# CANMosfetExtension.net
KiCad netlist of a schematic drawn in EAGLE
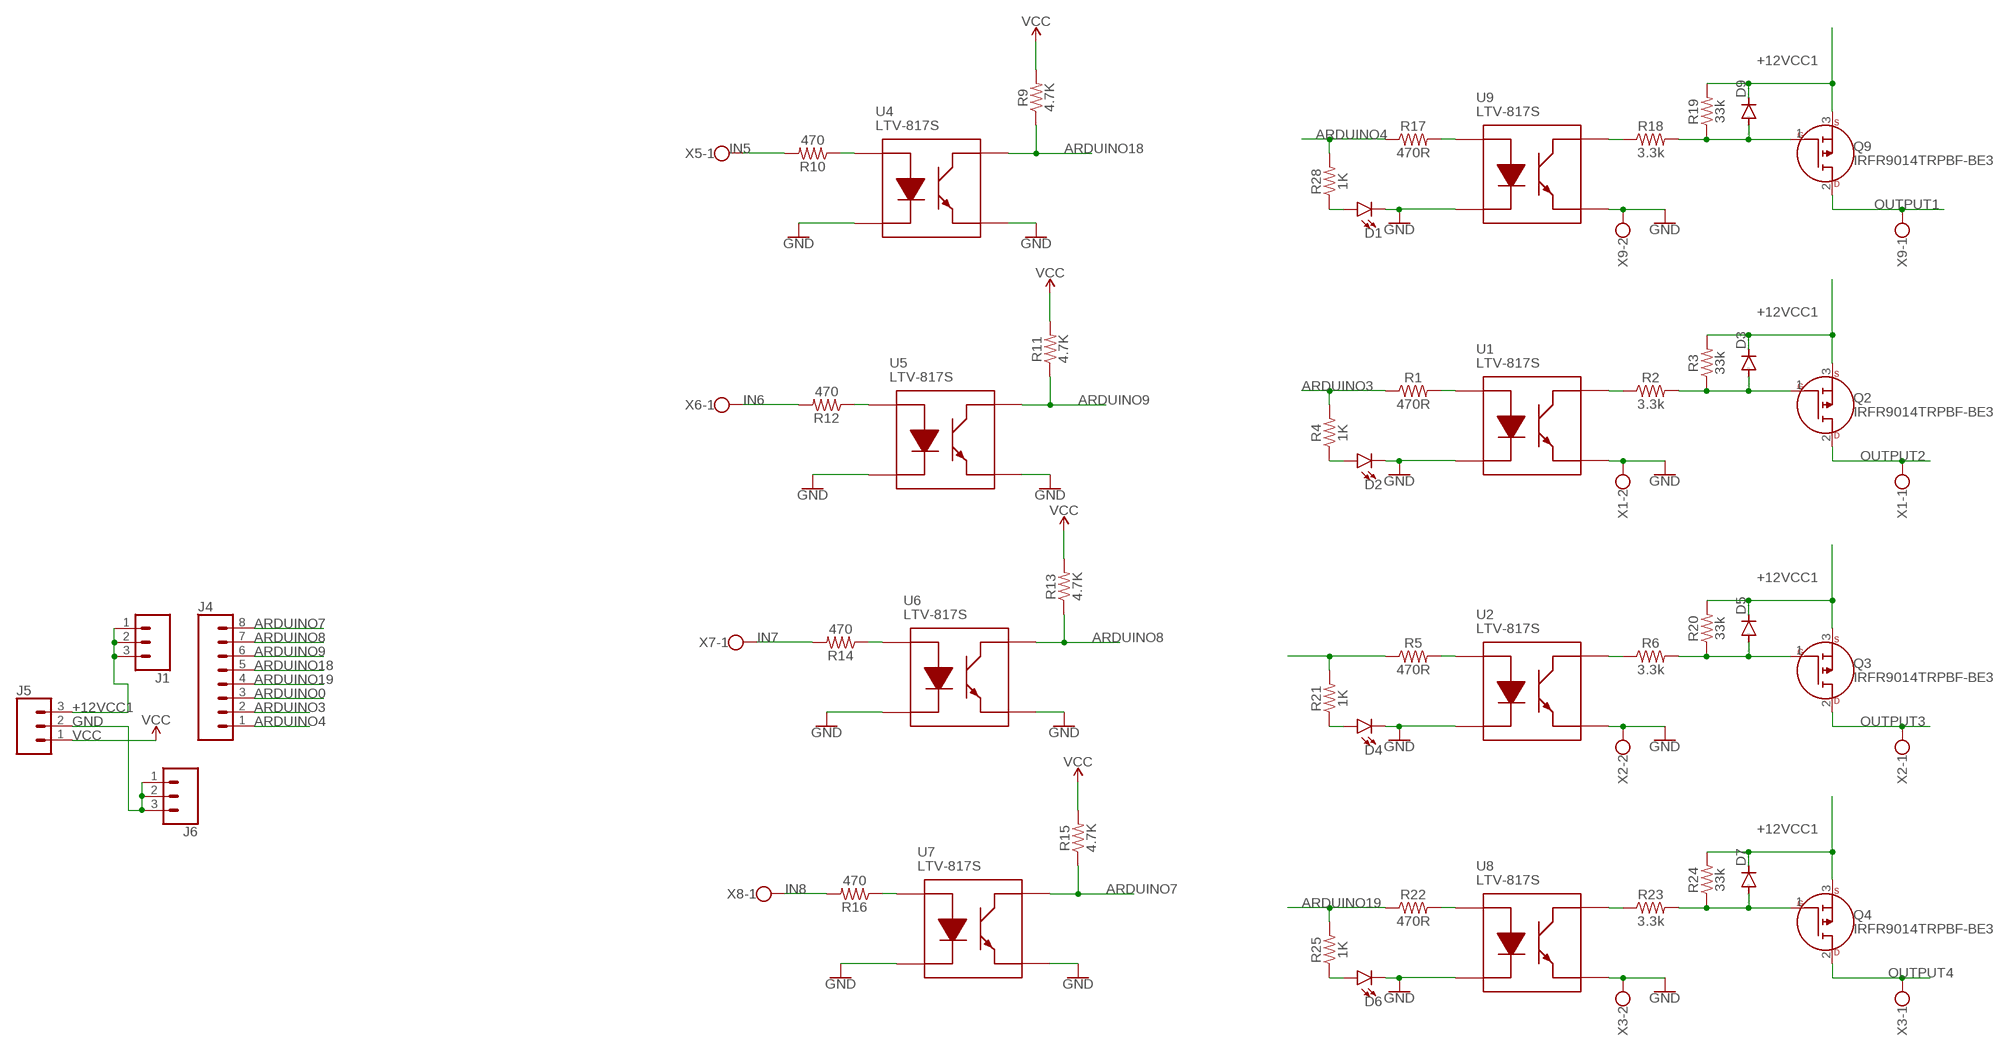
[diagram p0: schematic, sheet 1]

(export (version "E")
  (design (tool "Eeschema 10.0.6"))
  (components
    (comp (ref "D1")
      (value "LED0603")
      (footprint "eagle-import:LED-0603")
      (libsource (lib "eagle-import") (part "LED0603"))
    )
    (comp (ref "D2")
      (value "LED0603")
      (footprint "eagle-import:LED-0603")
      (libsource (lib "eagle-import") (part "LED0603"))
    )
    (comp (ref "D3")
      (value "DIODE-SOD123")
      (footprint "eagle-import:SOD123")
      (libsource (lib "eagle-import") (part "DIODE-SOD123"))
    )
    (comp (ref "D4")
      (value "LED0603")
      (footprint "eagle-import:LED-0603")
      (libsource (lib "eagle-import") (part "LED0603"))
    )
    (comp (ref "D5")
      (value "DIODE-SOD123")
      (footprint "eagle-import:SOD123")
      (libsource (lib "eagle-import") (part "DIODE-SOD123"))
    )
    (comp (ref "D6")
      (value "LED0603")
      (footprint "eagle-import:LED-0603")
      (libsource (lib "eagle-import") (part "LED0603"))
    )
    (comp (ref "D7")
      (value "DIODE-SOD123")
      (footprint "eagle-import:SOD123")
      (libsource (lib "eagle-import") (part "DIODE-SOD123"))
    )
    (comp (ref "D9")
      (value "DIODE-SOD123")
      (footprint "eagle-import:SOD123")
      (libsource (lib "eagle-import") (part "DIODE-SOD123"))
    )
    (comp (ref "J1")
      (value "CONN_03LOCK")
      (footprint "eagle-import:1X03_LOCK")
      (libsource (lib "eagle-import") (part "CONN_03LOCK"))
    )
    (comp (ref "J4")
      (value "CONN_08LOCK")
      (footprint "eagle-import:1X08_LOCK")
      (libsource (lib "eagle-import") (part "CONN_08LOCK"))
    )
    (comp (ref "J5")
      (value "CONN_03LOCK")
      (footprint "eagle-import:1X03_LOCK")
      (libsource (lib "eagle-import") (part "CONN_03LOCK"))
    )
    (comp (ref "J6")
      (value "CONN_03LOCK")
      (footprint "eagle-import:1X03_LOCK")
      (libsource (lib "eagle-import") (part "CONN_03LOCK"))
    )
    (comp (ref "Q2")
      (value "IRFR9014TRPBF-BE3")
      (footprint "eagle-import:IRFR9014TRPBFBE3")
      (fields (field (name "MOUSER_PART_NUMBER") "78-IRFR9014TRPBF-BE3"))
      (libsource (lib "eagle-import") (part "IRFR9014TRPBF-BE3"))
    )
    (comp (ref "Q3")
      (value "IRFR9014TRPBF-BE3")
      (footprint "eagle-import:IRFR9014TRPBFBE3")
      (fields (field (name "MOUSER_PART_NUMBER") "78-IRFR9014TRPBF-BE3"))
      (libsource (lib "eagle-import") (part "IRFR9014TRPBF-BE3"))
    )
    (comp (ref "Q4")
      (value "IRFR9014TRPBF-BE3")
      (footprint "eagle-import:IRFR9014TRPBFBE3")
      (fields (field (name "MOUSER_PART_NUMBER") "78-IRFR9014TRPBF-BE3"))
      (libsource (lib "eagle-import") (part "IRFR9014TRPBF-BE3"))
    )
    (comp (ref "Q9")
      (value "IRFR9014TRPBF-BE3")
      (footprint "eagle-import:IRFR9014TRPBFBE3")
      (fields (field (name "MOUSER_PART_NUMBER") "78-IRFR9014TRPBF-BE3"))
      (libsource (lib "eagle-import") (part "IRFR9014TRPBF-BE3"))
    )
    (comp (ref "R1")
      (value "470R")
      (footprint "eagle-import:0603")
      (libsource (lib "eagle-import") (part "1KOHM-0603-1/10W-1%"))
    )
    (comp (ref "R2")
      (value "3.3k")
      (footprint "eagle-import:0603")
      (libsource (lib "eagle-import") (part "1KOHM-0603-1/10W-1%"))
    )
    (comp (ref "R3")
      (value "33k")
      (footprint "eagle-import:0603")
      (libsource (lib "eagle-import") (part "1KOHM-0603-1/10W-1%"))
    )
    (comp (ref "R4")
      (value "1K")
      (footprint "eagle-import:0603")
      (libsource (lib "eagle-import") (part "1KOHM-0603-1/10W-1%"))
    )
    (comp (ref "R5")
      (value "470R")
      (footprint "eagle-import:0603")
      (libsource (lib "eagle-import") (part "1KOHM-0603-1/10W-1%"))
    )
    (comp (ref "R6")
      (value "3.3k")
      (footprint "eagle-import:0603")
      (libsource (lib "eagle-import") (part "1KOHM-0603-1/10W-1%"))
    )
    (comp (ref "R9")
      (value "4.7K")
      (footprint "eagle-import:0603")
      (libsource (lib "eagle-import") (part "1KOHM-0603-1/10W-1%"))
    )
    (comp (ref "R10")
      (value "470")
      (footprint "eagle-import:0603")
      (libsource (lib "eagle-import") (part "1KOHM-0603-1/10W-1%"))
    )
    (comp (ref "R11")
      (value "4.7K")
      (footprint "eagle-import:0603")
      (libsource (lib "eagle-import") (part "1KOHM-0603-1/10W-1%"))
    )
    (comp (ref "R12")
      (value "470")
      (footprint "eagle-import:0603")
      (libsource (lib "eagle-import") (part "1KOHM-0603-1/10W-1%"))
    )
    (comp (ref "R13")
      (value "4.7K")
      (footprint "eagle-import:0603")
      (libsource (lib "eagle-import") (part "1KOHM-0603-1/10W-1%"))
    )
    (comp (ref "R14")
      (value "470")
      (footprint "eagle-import:0603")
      (libsource (lib "eagle-import") (part "1KOHM-0603-1/10W-1%"))
    )
    (comp (ref "R15")
      (value "4.7K")
      (footprint "eagle-import:0603")
      (libsource (lib "eagle-import") (part "1KOHM-0603-1/10W-1%"))
    )
    (comp (ref "R16")
      (value "470")
      (footprint "eagle-import:0603")
      (libsource (lib "eagle-import") (part "1KOHM-0603-1/10W-1%"))
    )
    (comp (ref "R17")
      (value "470R")
      (footprint "eagle-import:0603")
      (libsource (lib "eagle-import") (part "1KOHM-0603-1/10W-1%"))
    )
    (comp (ref "R18")
      (value "3.3k")
      (footprint "eagle-import:0603")
      (libsource (lib "eagle-import") (part "1KOHM-0603-1/10W-1%"))
    )
    (comp (ref "R19")
      (value "33k")
      (footprint "eagle-import:0603")
      (libsource (lib "eagle-import") (part "1KOHM-0603-1/10W-1%"))
    )
    (comp (ref "R20")
      (value "33k")
      (footprint "eagle-import:0603")
      (libsource (lib "eagle-import") (part "1KOHM-0603-1/10W-1%"))
    )
    (comp (ref "R21")
      (value "1K")
      (footprint "eagle-import:0603")
      (libsource (lib "eagle-import") (part "1KOHM-0603-1/10W-1%"))
    )
    (comp (ref "R22")
      (value "470R")
      (footprint "eagle-import:0603")
      (libsource (lib "eagle-import") (part "1KOHM-0603-1/10W-1%"))
    )
    (comp (ref "R23")
      (value "3.3k")
      (footprint "eagle-import:0603")
      (libsource (lib "eagle-import") (part "1KOHM-0603-1/10W-1%"))
    )
    (comp (ref "R24")
      (value "33k")
      (footprint "eagle-import:0603")
      (libsource (lib "eagle-import") (part "1KOHM-0603-1/10W-1%"))
    )
    (comp (ref "R25")
      (value "1K")
      (footprint "eagle-import:0603")
      (libsource (lib "eagle-import") (part "1KOHM-0603-1/10W-1%"))
    )
    (comp (ref "R28")
      (value "1K")
      (footprint "eagle-import:0603")
      (libsource (lib "eagle-import") (part "1KOHM-0603-1/10W-1%"))
    )
    (comp (ref "U1")
      (value "LTV-817S")
      (footprint "eagle-import:SOP254P1016X460-4N")
      (fields (field (name "MOUSER_PART_NUMBER") "859-LTV-817S"))
      (libsource (lib "eagle-import") (part "LTV-817S"))
    )
    (comp (ref "U2")
      (value "LTV-817S")
      (footprint "eagle-import:SOP254P1016X460-4N")
      (fields (field (name "MOUSER_PART_NUMBER") "859-LTV-817S"))
      (libsource (lib "eagle-import") (part "LTV-817S"))
    )
    (comp (ref "U4")
      (value "LTV-817S")
      (footprint "eagle-import:SOP254P1016X460-4N")
      (fields (field (name "MOUSER_PART_NUMBER") "859-LTV-817S"))
      (libsource (lib "eagle-import") (part "LTV-817S"))
    )
    (comp (ref "U5")
      (value "LTV-817S")
      (footprint "eagle-import:SOP254P1016X460-4N")
      (fields (field (name "MOUSER_PART_NUMBER") "859-LTV-817S"))
      (libsource (lib "eagle-import") (part "LTV-817S"))
    )
    (comp (ref "U6")
      (value "LTV-817S")
      (footprint "eagle-import:SOP254P1016X460-4N")
      (fields (field (name "MOUSER_PART_NUMBER") "859-LTV-817S"))
      (libsource (lib "eagle-import") (part "LTV-817S"))
    )
    (comp (ref "U7")
      (value "LTV-817S")
      (footprint "eagle-import:SOP254P1016X460-4N")
      (fields (field (name "MOUSER_PART_NUMBER") "859-LTV-817S"))
      (libsource (lib "eagle-import") (part "LTV-817S"))
    )
    (comp (ref "U8")
      (value "LTV-817S")
      (footprint "eagle-import:SOP254P1016X460-4N")
      (fields (field (name "MOUSER_PART_NUMBER") "859-LTV-817S"))
      (libsource (lib "eagle-import") (part "LTV-817S"))
    )
    (comp (ref "U9")
      (value "LTV-817S")
      (footprint "eagle-import:SOP254P1016X460-4N")
      (fields (field (name "MOUSER_PART_NUMBER") "859-LTV-817S"))
      (libsource (lib "eagle-import") (part "LTV-817S"))
    )
    (comp (ref "X1")
      (value "W237-102")
      (footprint "eagle-import:W237-102")
      (fields (field (name "MPN") "237-102"))
      (libsource (lib "eagle-import") (part "W237-102"))
    )
    (comp (ref "X2")
      (value "W237-102")
      (footprint "eagle-import:W237-102")
      (fields (field (name "MPN") "237-102"))
      (libsource (lib "eagle-import") (part "W237-102"))
    )
    (comp (ref "X3")
      (value "W237-102")
      (footprint "eagle-import:W237-102")
      (fields (field (name "MPN") "237-102"))
      (libsource (lib "eagle-import") (part "W237-102"))
    )
    (comp (ref "X5")
      (value "W237-102")
      (footprint "eagle-import:W237-102")
      (fields (field (name "MPN") "237-102"))
      (libsource (lib "eagle-import") (part "W237-102"))
    )
    (comp (ref "X6")
      (value "W237-102")
      (footprint "eagle-import:W237-102")
      (fields (field (name "MPN") "237-102"))
      (libsource (lib "eagle-import") (part "W237-102"))
    )
    (comp (ref "X7")
      (value "W237-102")
      (footprint "eagle-import:W237-102")
      (fields (field (name "MPN") "237-102"))
      (libsource (lib "eagle-import") (part "W237-102"))
    )
    (comp (ref "X8")
      (value "W237-102")
      (footprint "eagle-import:W237-102")
      (fields (field (name "MPN") "237-102"))
      (libsource (lib "eagle-import") (part "W237-102"))
    )
    (comp (ref "X9")
      (value "W237-102")
      (footprint "eagle-import:W237-102")
      (fields (field (name "MPN") "237-102"))
      (libsource (lib "eagle-import") (part "W237-102"))
    )
  )
  (nets
    (net (code "1") (name "/+12VCC1") (class "Default")
      (node (ref "D3") (pin "C") (pinfunction "C_C") (pintype "passive"))
      (node (ref "D5") (pin "C") (pinfunction "C_C") (pintype "passive"))
      (node (ref "D7") (pin "C") (pinfunction "C_C") (pintype "passive"))
      (node (ref "D9") (pin "C") (pinfunction "C_C") (pintype "passive"))
      (node (ref "J1") (pin "1") (pinfunction "1_1") (pintype "passive"))
      (node (ref "J1") (pin "2") (pinfunction "2_2") (pintype "passive"))
      (node (ref "J1") (pin "3") (pinfunction "3_3") (pintype "passive"))
      (node (ref "J5") (pin "3") (pinfunction "3_3") (pintype "passive"))
      (node (ref "Q2") (pin "3") (pinfunction "D_3") (pintype "bidirectional"))
      (node (ref "Q3") (pin "3") (pinfunction "D_3") (pintype "bidirectional"))
      (node (ref "Q4") (pin "3") (pinfunction "D_3") (pintype "bidirectional"))
      (node (ref "Q9") (pin "3") (pinfunction "D_3") (pintype "bidirectional"))
      (node (ref "R19") (pin "2") (pinfunction "2_2") (pintype "passive"))
      (node (ref "R20") (pin "2") (pinfunction "2_2") (pintype "passive"))
      (node (ref "R24") (pin "2") (pinfunction "2_2") (pintype "passive"))
      (node (ref "R3") (pin "2") (pinfunction "2_2") (pintype "passive"))
    )
    (net (code "2") (name "/ARDUINO0") (class "Default")
      (node (ref "J4") (pin "3") (pinfunction "3_3") (pintype "passive"))
      (node (ref "R21") (pin "2") (pinfunction "2_2") (pintype "passive"))
      (node (ref "R5") (pin "1") (pinfunction "1_1") (pintype "passive"))
    )
    (net (code "3") (name "/ARDUINO3") (class "Default")
      (node (ref "J4") (pin "2") (pinfunction "2_2") (pintype "passive"))
      (node (ref "R1") (pin "1") (pinfunction "1_1") (pintype "passive"))
      (node (ref "R4") (pin "2") (pinfunction "2_2") (pintype "passive"))
    )
    (net (code "4") (name "/ARDUINO4") (class "Default")
      (node (ref "J4") (pin "1") (pinfunction "1_1") (pintype "passive"))
      (node (ref "R17") (pin "1") (pinfunction "1_1") (pintype "passive"))
      (node (ref "R28") (pin "2") (pinfunction "2_2") (pintype "passive"))
    )
    (net (code "5") (name "/ARDUINO7") (class "Default")
      (node (ref "J4") (pin "8") (pinfunction "8_8") (pintype "passive"))
      (node (ref "R15") (pin "1") (pinfunction "1_1") (pintype "passive"))
      (node (ref "U7") (pin "4") (pinfunction "COLLECTOR_4") (pintype "bidirectional"))
    )
    (net (code "6") (name "/ARDUINO8") (class "Default")
      (node (ref "J4") (pin "7") (pinfunction "7_7") (pintype "passive"))
      (node (ref "R13") (pin "1") (pinfunction "1_1") (pintype "passive"))
      (node (ref "U6") (pin "4") (pinfunction "COLLECTOR_4") (pintype "bidirectional"))
    )
    (net (code "7") (name "/ARDUINO9") (class "Default")
      (node (ref "J4") (pin "6") (pinfunction "6_6") (pintype "passive"))
      (node (ref "R11") (pin "1") (pinfunction "1_1") (pintype "passive"))
      (node (ref "U5") (pin "4") (pinfunction "COLLECTOR_4") (pintype "bidirectional"))
    )
    (net (code "8") (name "/ARDUINO18") (class "Default")
      (node (ref "J4") (pin "5") (pinfunction "5_5") (pintype "passive"))
      (node (ref "R9") (pin "1") (pinfunction "1_1") (pintype "passive"))
      (node (ref "U4") (pin "4") (pinfunction "COLLECTOR_4") (pintype "bidirectional"))
    )
    (net (code "9") (name "/ARDUINO19") (class "Default")
      (node (ref "J4") (pin "4") (pinfunction "4_4") (pintype "passive"))
      (node (ref "R22") (pin "1") (pinfunction "1_1") (pintype "passive"))
      (node (ref "R25") (pin "2") (pinfunction "2_2") (pintype "passive"))
    )
    (net (code "10") (name "/IN5") (class "Default")
      (node (ref "R10") (pin "2") (pinfunction "2_2") (pintype "passive"))
      (node (ref "X5") (pin "1") (pinfunction "KL_1") (pintype "passive"))
    )
    (net (code "11") (name "/IN6") (class "Default")
      (node (ref "R12") (pin "2") (pinfunction "2_2") (pintype "passive"))
      (node (ref "X6") (pin "1") (pinfunction "KL_1") (pintype "passive"))
    )
    (net (code "12") (name "/IN7") (class "Default")
      (node (ref "R14") (pin "2") (pinfunction "2_2") (pintype "passive"))
      (node (ref "X7") (pin "1") (pinfunction "KL_1") (pintype "passive"))
    )
    (net (code "13") (name "/IN8") (class "Default")
      (node (ref "R16") (pin "2") (pinfunction "2_2") (pintype "passive"))
      (node (ref "X8") (pin "1") (pinfunction "KL_1") (pintype "passive"))
    )
    (net (code "14") (name "/OUTPUT1") (class "Default")
      (node (ref "Q9") (pin "2") (pinfunction "S_2") (pintype "bidirectional"))
      (node (ref "X9") (pin "1") (pinfunction "KL_1") (pintype "passive"))
    )
    (net (code "15") (name "/OUTPUT2") (class "Default")
      (node (ref "Q2") (pin "2") (pinfunction "S_2") (pintype "bidirectional"))
      (node (ref "X1") (pin "1") (pinfunction "KL_1") (pintype "passive"))
    )
    (net (code "16") (name "/OUTPUT3") (class "Default")
      (node (ref "Q3") (pin "2") (pinfunction "S_2") (pintype "bidirectional"))
      (node (ref "X2") (pin "1") (pinfunction "KL_1") (pintype "passive"))
    )
    (net (code "17") (name "/OUTPUT4") (class "Default")
      (node (ref "Q4") (pin "2") (pinfunction "S_2") (pintype "bidirectional"))
      (node (ref "X3") (pin "1") (pinfunction "KL_1") (pintype "passive"))
    )
    (net (code "18") (name "GND") (class "Default")
      (node (ref "D1") (pin "C") (pinfunction "C_C") (pintype "passive"))
      (node (ref "D2") (pin "C") (pinfunction "C_C") (pintype "passive"))
      (node (ref "D4") (pin "C") (pinfunction "C_C") (pintype "passive"))
      (node (ref "D6") (pin "C") (pinfunction "C_C") (pintype "passive"))
      (node (ref "J5") (pin "2") (pinfunction "2_2") (pintype "passive"))
      (node (ref "J6") (pin "1") (pinfunction "1_1") (pintype "passive"))
      (node (ref "J6") (pin "2") (pinfunction "2_2") (pintype "passive"))
      (node (ref "J6") (pin "3") (pinfunction "3_3") (pintype "passive"))
      (node (ref "U1") (pin "2") (pinfunction "CATHODE_2") (pintype "bidirectional"))
      (node (ref "U1") (pin "3") (pinfunction "EMITTER_3") (pintype "bidirectional"))
      (node (ref "U2") (pin "2") (pinfunction "CATHODE_2") (pintype "bidirectional"))
      (node (ref "U2") (pin "3") (pinfunction "EMITTER_3") (pintype "bidirectional"))
      (node (ref "U4") (pin "2") (pinfunction "CATHODE_2") (pintype "bidirectional"))
      (node (ref "U4") (pin "3") (pinfunction "EMITTER_3") (pintype "bidirectional"))
      (node (ref "U5") (pin "2") (pinfunction "CATHODE_2") (pintype "bidirectional"))
      (node (ref "U5") (pin "3") (pinfunction "EMITTER_3") (pintype "bidirectional"))
      (node (ref "U6") (pin "2") (pinfunction "CATHODE_2") (pintype "bidirectional"))
      (node (ref "U6") (pin "3") (pinfunction "EMITTER_3") (pintype "bidirectional"))
      (node (ref "U7") (pin "2") (pinfunction "CATHODE_2") (pintype "bidirectional"))
      (node (ref "U7") (pin "3") (pinfunction "EMITTER_3") (pintype "bidirectional"))
      (node (ref "U8") (pin "2") (pinfunction "CATHODE_2") (pintype "bidirectional"))
      (node (ref "U8") (pin "3") (pinfunction "EMITTER_3") (pintype "bidirectional"))
      (node (ref "U9") (pin "2") (pinfunction "CATHODE_2") (pintype "bidirectional"))
      (node (ref "U9") (pin "3") (pinfunction "EMITTER_3") (pintype "bidirectional"))
      (node (ref "X1") (pin "2") (pinfunction "KL_2") (pintype "passive"))
      (node (ref "X2") (pin "2") (pinfunction "KL_2") (pintype "passive"))
      (node (ref "X3") (pin "2") (pinfunction "KL_2") (pintype "passive"))
      (node (ref "X9") (pin "2") (pinfunction "KL_2") (pintype "passive"))
    )
    (net (code "19") (name "Net-(D1-PadA)") (class "Default")
      (node (ref "D1") (pin "A") (pinfunction "A_A") (pintype "passive"))
      (node (ref "R28") (pin "1") (pinfunction "1_1") (pintype "passive"))
    )
    (net (code "20") (name "Net-(D2-PadA)") (class "Default")
      (node (ref "D2") (pin "A") (pinfunction "A_A") (pintype "passive"))
      (node (ref "R4") (pin "1") (pinfunction "1_1") (pintype "passive"))
    )
    (net (code "21") (name "Net-(D4-PadA)") (class "Default")
      (node (ref "D4") (pin "A") (pinfunction "A_A") (pintype "passive"))
      (node (ref "R21") (pin "1") (pinfunction "1_1") (pintype "passive"))
    )
    (net (code "22") (name "Net-(D6-PadA)") (class "Default")
      (node (ref "D6") (pin "A") (pinfunction "A_A") (pintype "passive"))
      (node (ref "R25") (pin "1") (pinfunction "1_1") (pintype "passive"))
    )
    (net (code "23") (name "Net-(Q2-G)") (class "Default")
      (node (ref "D3") (pin "A") (pinfunction "A_A") (pintype "passive"))
      (node (ref "Q2") (pin "1") (pinfunction "G_1") (pintype "bidirectional"))
      (node (ref "R2") (pin "2") (pinfunction "2_2") (pintype "passive"))
      (node (ref "R3") (pin "1") (pinfunction "1_1") (pintype "passive"))
    )
    (net (code "24") (name "Net-(Q3-G)") (class "Default")
      (node (ref "D5") (pin "A") (pinfunction "A_A") (pintype "passive"))
      (node (ref "Q3") (pin "1") (pinfunction "G_1") (pintype "bidirectional"))
      (node (ref "R20") (pin "1") (pinfunction "1_1") (pintype "passive"))
      (node (ref "R6") (pin "2") (pinfunction "2_2") (pintype "passive"))
    )
    (net (code "25") (name "Net-(Q4-G)") (class "Default")
      (node (ref "D7") (pin "A") (pinfunction "A_A") (pintype "passive"))
      (node (ref "Q4") (pin "1") (pinfunction "G_1") (pintype "bidirectional"))
      (node (ref "R23") (pin "2") (pinfunction "2_2") (pintype "passive"))
      (node (ref "R24") (pin "1") (pinfunction "1_1") (pintype "passive"))
    )
    (net (code "26") (name "Net-(Q9-G)") (class "Default")
      (node (ref "D9") (pin "A") (pinfunction "A_A") (pintype "passive"))
      (node (ref "Q9") (pin "1") (pinfunction "G_1") (pintype "bidirectional"))
      (node (ref "R18") (pin "2") (pinfunction "2_2") (pintype "passive"))
      (node (ref "R19") (pin "1") (pinfunction "1_1") (pintype "passive"))
    )
    (net (code "27") (name "Net-(U1-ANODE)") (class "Default")
      (node (ref "R1") (pin "2") (pinfunction "2_2") (pintype "passive"))
      (node (ref "U1") (pin "1") (pinfunction "ANODE_1") (pintype "bidirectional"))
    )
    (net (code "28") (name "Net-(U1-COLLECTOR)") (class "Default")
      (node (ref "R2") (pin "1") (pinfunction "1_1") (pintype "passive"))
      (node (ref "U1") (pin "4") (pinfunction "COLLECTOR_4") (pintype "bidirectional"))
    )
    (net (code "29") (name "Net-(U2-ANODE)") (class "Default")
      (node (ref "R5") (pin "2") (pinfunction "2_2") (pintype "passive"))
      (node (ref "U2") (pin "1") (pinfunction "ANODE_1") (pintype "bidirectional"))
    )
    (net (code "30") (name "Net-(U2-COLLECTOR)") (class "Default")
      (node (ref "R6") (pin "1") (pinfunction "1_1") (pintype "passive"))
      (node (ref "U2") (pin "4") (pinfunction "COLLECTOR_4") (pintype "bidirectional"))
    )
    (net (code "31") (name "Net-(U4-ANODE)") (class "Default")
      (node (ref "R10") (pin "1") (pinfunction "1_1") (pintype "passive"))
      (node (ref "U4") (pin "1") (pinfunction "ANODE_1") (pintype "bidirectional"))
    )
    (net (code "32") (name "Net-(U5-ANODE)") (class "Default")
      (node (ref "R12") (pin "1") (pinfunction "1_1") (pintype "passive"))
      (node (ref "U5") (pin "1") (pinfunction "ANODE_1") (pintype "bidirectional"))
    )
    (net (code "33") (name "Net-(U6-ANODE)") (class "Default")
      (node (ref "R14") (pin "1") (pinfunction "1_1") (pintype "passive"))
      (node (ref "U6") (pin "1") (pinfunction "ANODE_1") (pintype "bidirectional"))
    )
    (net (code "34") (name "Net-(U7-ANODE)") (class "Default")
      (node (ref "R16") (pin "1") (pinfunction "1_1") (pintype "passive"))
      (node (ref "U7") (pin "1") (pinfunction "ANODE_1") (pintype "bidirectional"))
    )
    (net (code "35") (name "Net-(U8-ANODE)") (class "Default")
      (node (ref "R22") (pin "2") (pinfunction "2_2") (pintype "passive"))
      (node (ref "U8") (pin "1") (pinfunction "ANODE_1") (pintype "bidirectional"))
    )
    (net (code "36") (name "Net-(U8-COLLECTOR)") (class "Default")
      (node (ref "R23") (pin "1") (pinfunction "1_1") (pintype "passive"))
      (node (ref "U8") (pin "4") (pinfunction "COLLECTOR_4") (pintype "bidirectional"))
    )
    (net (code "37") (name "Net-(U9-ANODE)") (class "Default")
      (node (ref "R17") (pin "2") (pinfunction "2_2") (pintype "passive"))
      (node (ref "U9") (pin "1") (pinfunction "ANODE_1") (pintype "bidirectional"))
    )
    (net (code "38") (name "Net-(U9-COLLECTOR)") (class "Default")
      (node (ref "R18") (pin "1") (pinfunction "1_1") (pintype "passive"))
      (node (ref "U9") (pin "4") (pinfunction "COLLECTOR_4") (pintype "bidirectional"))
    )
    (net (code "39") (name "VCC") (class "Default")
      (node (ref "J5") (pin "1") (pinfunction "1_1") (pintype "passive"))
      (node (ref "R11") (pin "2") (pinfunction "2_2") (pintype "passive"))
      (node (ref "R13") (pin "2") (pinfunction "2_2") (pintype "passive"))
      (node (ref "R15") (pin "2") (pinfunction "2_2") (pintype "passive"))
      (node (ref "R9") (pin "2") (pinfunction "2_2") (pintype "passive"))
    )
  )
)
